# Output.net
KiCad netlist of a schematic drawn in Altium Designer
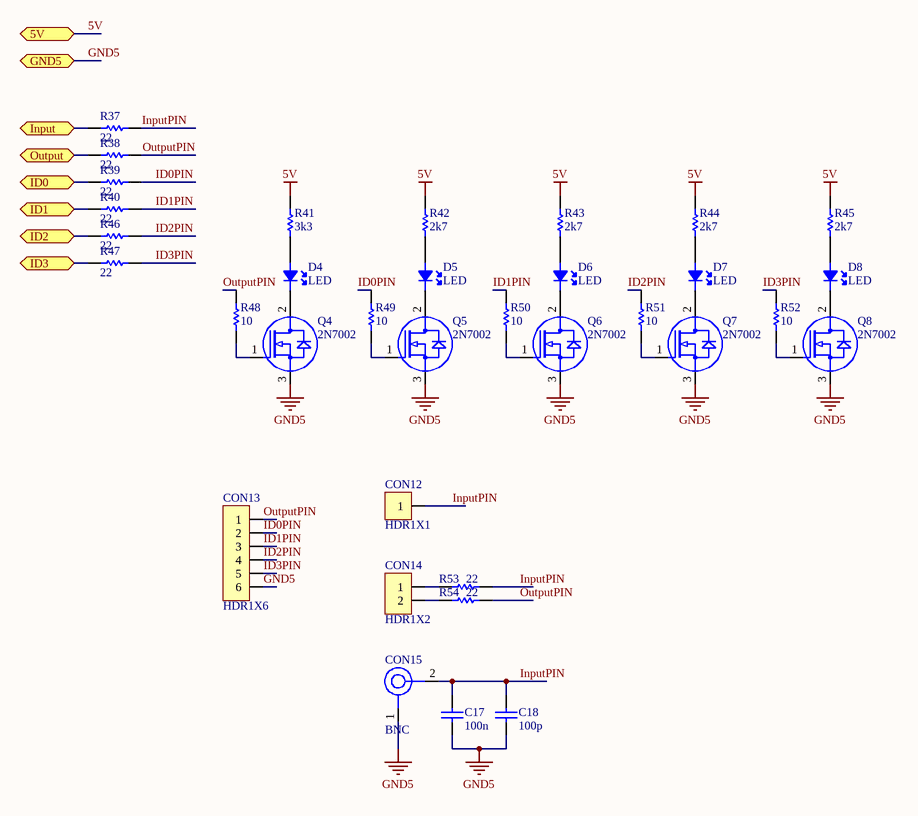
[diagram p0: Output.SchDoc]

(export (version "E")
  (design (tool "Eeschema 10.0.6"))
  (components
    (comp (ref "C17")
      (value "100n")
      (footprint "dimploma:0805C")
      (libsource (lib "diploma") (part "CAPACITOR"))
    )
    (comp (ref "C18")
      (value "100p")
      (footprint "dimploma:0805C")
      (libsource (lib "diploma") (part "CAPACITOR"))
    )
    (comp (ref "CON12")
      (value "HDR1X1")
      (footprint "dimploma:HDR1X1")
      (libsource (lib "diploma") (part "HDR1X1"))
    )
    (comp (ref "CON13")
      (value "HDR1X6")
      (footprint "dimploma:HDR1X6RAST")
      (libsource (lib "diploma") (part "HDR1X6"))
    )
    (comp (ref "CON14")
      (value "HDR1X2")
      (footprint "dimploma:HDR1X2RAST")
      (libsource (lib "diploma") (part "HDR1X2"))
    )
    (comp (ref "CON15") (value "BNC") (footprint "dimploma:BNC_THD") (libsource (lib "diploma") (part "BNC")))
    (comp (ref "D4") (value "LED") (footprint "dimploma:0805LED") (libsource (lib "diploma") (part "LED")))
    (comp (ref "D5") (value "LED") (footprint "dimploma:0805LED") (libsource (lib "diploma") (part "LED")))
    (comp (ref "D6") (value "LED") (footprint "dimploma:0805LED") (libsource (lib "diploma") (part "LED")))
    (comp (ref "D7") (value "LED") (footprint "dimploma:0805LED") (libsource (lib "diploma") (part "LED")))
    (comp (ref "D8") (value "LED") (footprint "dimploma:0805LED") (libsource (lib "diploma") (part "LED")))
    (comp (ref "Q4")
      (value "2N7002")
      (footprint "dimploma:SOT23")
      (libsource (lib "diploma") (part "2N7002"))
    )
    (comp (ref "Q5")
      (value "2N7002")
      (footprint "dimploma:SOT23")
      (libsource (lib "diploma") (part "2N7002"))
    )
    (comp (ref "Q6")
      (value "2N7002")
      (footprint "dimploma:SOT23")
      (libsource (lib "diploma") (part "2N7002"))
    )
    (comp (ref "Q7")
      (value "2N7002")
      (footprint "dimploma:SOT23")
      (libsource (lib "diploma") (part "2N7002"))
    )
    (comp (ref "Q8")
      (value "2N7002")
      (footprint "dimploma:SOT23")
      (libsource (lib "diploma") (part "2N7002"))
    )
    (comp (ref "R37") (value "22") (footprint "dimploma:0805R") (libsource (lib "diploma") (part "RESISTOR")))
    (comp (ref "R38") (value "22") (footprint "dimploma:0805R") (libsource (lib "diploma") (part "RESISTOR")))
    (comp (ref "R39") (value "22") (footprint "dimploma:0805R") (libsource (lib "diploma") (part "RESISTOR")))
    (comp (ref "R40") (value "22") (footprint "dimploma:0805R") (libsource (lib "diploma") (part "RESISTOR")))
    (comp (ref "R41")
      (value "3k3")
      (footprint "dimploma:0805R")
      (libsource (lib "diploma") (part "RESISTOR"))
    )
    (comp (ref "R42")
      (value "2k7")
      (footprint "dimploma:0805R")
      (libsource (lib "diploma") (part "RESISTOR"))
    )
    (comp (ref "R43")
      (value "2k7")
      (footprint "dimploma:0805R")
      (libsource (lib "diploma") (part "RESISTOR"))
    )
    (comp (ref "R44")
      (value "2k7")
      (footprint "dimploma:0805R")
      (libsource (lib "diploma") (part "RESISTOR"))
    )
    (comp (ref "R45")
      (value "2k7")
      (footprint "dimploma:0805R")
      (libsource (lib "diploma") (part "RESISTOR"))
    )
    (comp (ref "R46") (value "22") (footprint "dimploma:0805R") (libsource (lib "diploma") (part "RESISTOR")))
    (comp (ref "R47") (value "22") (footprint "dimploma:0805R") (libsource (lib "diploma") (part "RESISTOR")))
    (comp (ref "R48") (value "10") (footprint "dimploma:0805R") (libsource (lib "diploma") (part "RESISTOR")))
    (comp (ref "R49") (value "10") (footprint "dimploma:0805R") (libsource (lib "diploma") (part "RESISTOR")))
    (comp (ref "R50") (value "10") (footprint "dimploma:0805R") (libsource (lib "diploma") (part "RESISTOR")))
    (comp (ref "R51") (value "10") (footprint "dimploma:0805R") (libsource (lib "diploma") (part "RESISTOR")))
    (comp (ref "R52") (value "10") (footprint "dimploma:0805R") (libsource (lib "diploma") (part "RESISTOR")))
    (comp (ref "R53") (value "22") (footprint "dimploma:0805R") (libsource (lib "diploma") (part "RESISTOR")))
    (comp (ref "R54") (value "22") (footprint "dimploma:0805R") (libsource (lib "diploma") (part "RESISTOR")))
  )
  (nets
    (net (code "1") (name "/ID0") (class "Default")
      (node (ref "R39") (pin "1") (pinfunction "1_1") (pintype "passive"))
    )
    (net (code "2") (name "/ID0PIN") (class "Default")
      (node (ref "CON13") (pin "2") (pinfunction "2_2") (pintype "passive"))
      (node (ref "R39") (pin "2") (pinfunction "2_2") (pintype "passive"))
      (node (ref "R49") (pin "2") (pinfunction "2_2") (pintype "passive"))
    )
    (net (code "3") (name "/ID1") (class "Default")
      (node (ref "R40") (pin "1") (pinfunction "1_1") (pintype "passive"))
    )
    (net (code "4") (name "/ID1PIN") (class "Default")
      (node (ref "CON13") (pin "3") (pinfunction "3_3") (pintype "passive"))
      (node (ref "R40") (pin "2") (pinfunction "2_2") (pintype "passive"))
      (node (ref "R50") (pin "2") (pinfunction "2_2") (pintype "passive"))
    )
    (net (code "5") (name "/ID2") (class "Default")
      (node (ref "R46") (pin "1") (pinfunction "1_1") (pintype "passive"))
    )
    (net (code "6") (name "/ID2PIN") (class "Default")
      (node (ref "CON13") (pin "4") (pinfunction "4_4") (pintype "passive"))
      (node (ref "R46") (pin "2") (pinfunction "2_2") (pintype "passive"))
      (node (ref "R51") (pin "2") (pinfunction "2_2") (pintype "passive"))
    )
    (net (code "7") (name "/ID3") (class "Default")
      (node (ref "R47") (pin "1") (pinfunction "1_1") (pintype "passive"))
    )
    (net (code "8") (name "/ID3PIN") (class "Default")
      (node (ref "CON13") (pin "5") (pinfunction "5_5") (pintype "passive"))
      (node (ref "R47") (pin "2") (pinfunction "2_2") (pintype "passive"))
      (node (ref "R52") (pin "2") (pinfunction "2_2") (pintype "passive"))
    )
    (net (code "9") (name "/Input") (class "Default")
      (node (ref "R37") (pin "1") (pinfunction "1_1") (pintype "passive"))
    )
    (net (code "10") (name "/InputPIN") (class "Default")
      (node (ref "C17") (pin "2") (pinfunction "2_2") (pintype "passive"))
      (node (ref "C18") (pin "2") (pinfunction "2_2") (pintype "passive"))
      (node (ref "CON12") (pin "1") (pinfunction "1_1") (pintype "passive"))
      (node (ref "CON15") (pin "2") (pintype "passive"))
      (node (ref "R37") (pin "2") (pinfunction "2_2") (pintype "passive"))
      (node (ref "R53") (pin "2") (pinfunction "2_2") (pintype "passive"))
    )
    (net (code "11") (name "/Output") (class "Default")
      (node (ref "R38") (pin "1") (pinfunction "1_1") (pintype "passive"))
    )
    (net (code "12") (name "/OutputPIN") (class "Default")
      (node (ref "CON13") (pin "1") (pinfunction "1_1") (pintype "passive"))
      (node (ref "R38") (pin "2") (pinfunction "2_2") (pintype "passive"))
      (node (ref "R48") (pin "2") (pinfunction "2_2") (pintype "passive"))
      (node (ref "R54") (pin "2") (pinfunction "2_2") (pintype "passive"))
    )
    (net (code "13") (name "5V") (class "Default")
      (node (ref "R41") (pin "2") (pinfunction "2_2") (pintype "passive"))
      (node (ref "R42") (pin "2") (pinfunction "2_2") (pintype "passive"))
      (node (ref "R43") (pin "2") (pinfunction "2_2") (pintype "passive"))
      (node (ref "R44") (pin "2") (pinfunction "2_2") (pintype "passive"))
      (node (ref "R45") (pin "2") (pinfunction "2_2") (pintype "passive"))
    )
    (net (code "14") (name "GND5") (class "Default")
      (node (ref "C17") (pin "1") (pinfunction "1_1") (pintype "passive"))
      (node (ref "C18") (pin "1") (pinfunction "1_1") (pintype "passive"))
      (node (ref "CON13") (pin "6") (pinfunction "6_6") (pintype "passive"))
      (node (ref "CON15") (pin "1") (pintype "passive"))
      (node (ref "Q4") (pin "3") (pinfunction "SOURCE_3") (pintype "passive"))
      (node (ref "Q5") (pin "3") (pinfunction "SOURCE_3") (pintype "passive"))
      (node (ref "Q6") (pin "3") (pinfunction "SOURCE_3") (pintype "passive"))
      (node (ref "Q7") (pin "3") (pinfunction "SOURCE_3") (pintype "passive"))
      (node (ref "Q8") (pin "3") (pinfunction "SOURCE_3") (pintype "passive"))
    )
    (net (code "15") (name "Net-(CON14-Pad1)") (class "Default")
      (node (ref "CON14") (pin "1") (pinfunction "1_1") (pintype "passive"))
      (node (ref "R53") (pin "1") (pinfunction "1_1") (pintype "passive"))
    )
    (net (code "16") (name "Net-(CON14-Pad2)") (class "Default")
      (node (ref "CON14") (pin "2") (pinfunction "2_2") (pintype "passive"))
      (node (ref "R54") (pin "1") (pinfunction "1_1") (pintype "passive"))
    )
    (net (code "17") (name "Net-(D4-A)") (class "Default")
      (node (ref "D4") (pin "1") (pinfunction "A_1") (pintype "passive"))
      (node (ref "R41") (pin "1") (pinfunction "1_1") (pintype "passive"))
    )
    (net (code "18") (name "Net-(D4-K)") (class "Default")
      (node (ref "D4") (pin "2") (pinfunction "K_2") (pintype "passive"))
      (node (ref "Q4") (pin "2") (pinfunction "DRAIN_2") (pintype "passive"))
    )
    (net (code "19") (name "Net-(D5-A)") (class "Default")
      (node (ref "D5") (pin "1") (pinfunction "A_1") (pintype "passive"))
      (node (ref "R42") (pin "1") (pinfunction "1_1") (pintype "passive"))
    )
    (net (code "20") (name "Net-(D5-K)") (class "Default")
      (node (ref "D5") (pin "2") (pinfunction "K_2") (pintype "passive"))
      (node (ref "Q5") (pin "2") (pinfunction "DRAIN_2") (pintype "passive"))
    )
    (net (code "21") (name "Net-(D6-A)") (class "Default")
      (node (ref "D6") (pin "1") (pinfunction "A_1") (pintype "passive"))
      (node (ref "R43") (pin "1") (pinfunction "1_1") (pintype "passive"))
    )
    (net (code "22") (name "Net-(D6-K)") (class "Default")
      (node (ref "D6") (pin "2") (pinfunction "K_2") (pintype "passive"))
      (node (ref "Q6") (pin "2") (pinfunction "DRAIN_2") (pintype "passive"))
    )
    (net (code "23") (name "Net-(D7-A)") (class "Default")
      (node (ref "D7") (pin "1") (pinfunction "A_1") (pintype "passive"))
      (node (ref "R44") (pin "1") (pinfunction "1_1") (pintype "passive"))
    )
    (net (code "24") (name "Net-(D7-K)") (class "Default")
      (node (ref "D7") (pin "2") (pinfunction "K_2") (pintype "passive"))
      (node (ref "Q7") (pin "2") (pinfunction "DRAIN_2") (pintype "passive"))
    )
    (net (code "25") (name "Net-(D8-A)") (class "Default")
      (node (ref "D8") (pin "1") (pinfunction "A_1") (pintype "passive"))
      (node (ref "R45") (pin "1") (pinfunction "1_1") (pintype "passive"))
    )
    (net (code "26") (name "Net-(D8-K)") (class "Default")
      (node (ref "D8") (pin "2") (pinfunction "K_2") (pintype "passive"))
      (node (ref "Q8") (pin "2") (pinfunction "DRAIN_2") (pintype "passive"))
    )
    (net (code "27") (name "Net-(Q4-GATE)") (class "Default")
      (node (ref "Q4") (pin "1") (pinfunction "GATE_1") (pintype "passive"))
      (node (ref "R48") (pin "1") (pinfunction "1_1") (pintype "passive"))
    )
    (net (code "28") (name "Net-(Q5-GATE)") (class "Default")
      (node (ref "Q5") (pin "1") (pinfunction "GATE_1") (pintype "passive"))
      (node (ref "R49") (pin "1") (pinfunction "1_1") (pintype "passive"))
    )
    (net (code "29") (name "Net-(Q6-GATE)") (class "Default")
      (node (ref "Q6") (pin "1") (pinfunction "GATE_1") (pintype "passive"))
      (node (ref "R50") (pin "1") (pinfunction "1_1") (pintype "passive"))
    )
    (net (code "30") (name "Net-(Q7-GATE)") (class "Default")
      (node (ref "Q7") (pin "1") (pinfunction "GATE_1") (pintype "passive"))
      (node (ref "R51") (pin "1") (pinfunction "1_1") (pintype "passive"))
    )
    (net (code "31") (name "Net-(Q8-GATE)") (class "Default")
      (node (ref "Q8") (pin "1") (pinfunction "GATE_1") (pintype "passive"))
      (node (ref "R52") (pin "1") (pinfunction "1_1") (pintype "passive"))
    )
  )
)
